# POW.net
KiCad netlist of a schematic drawn in Altium Designer
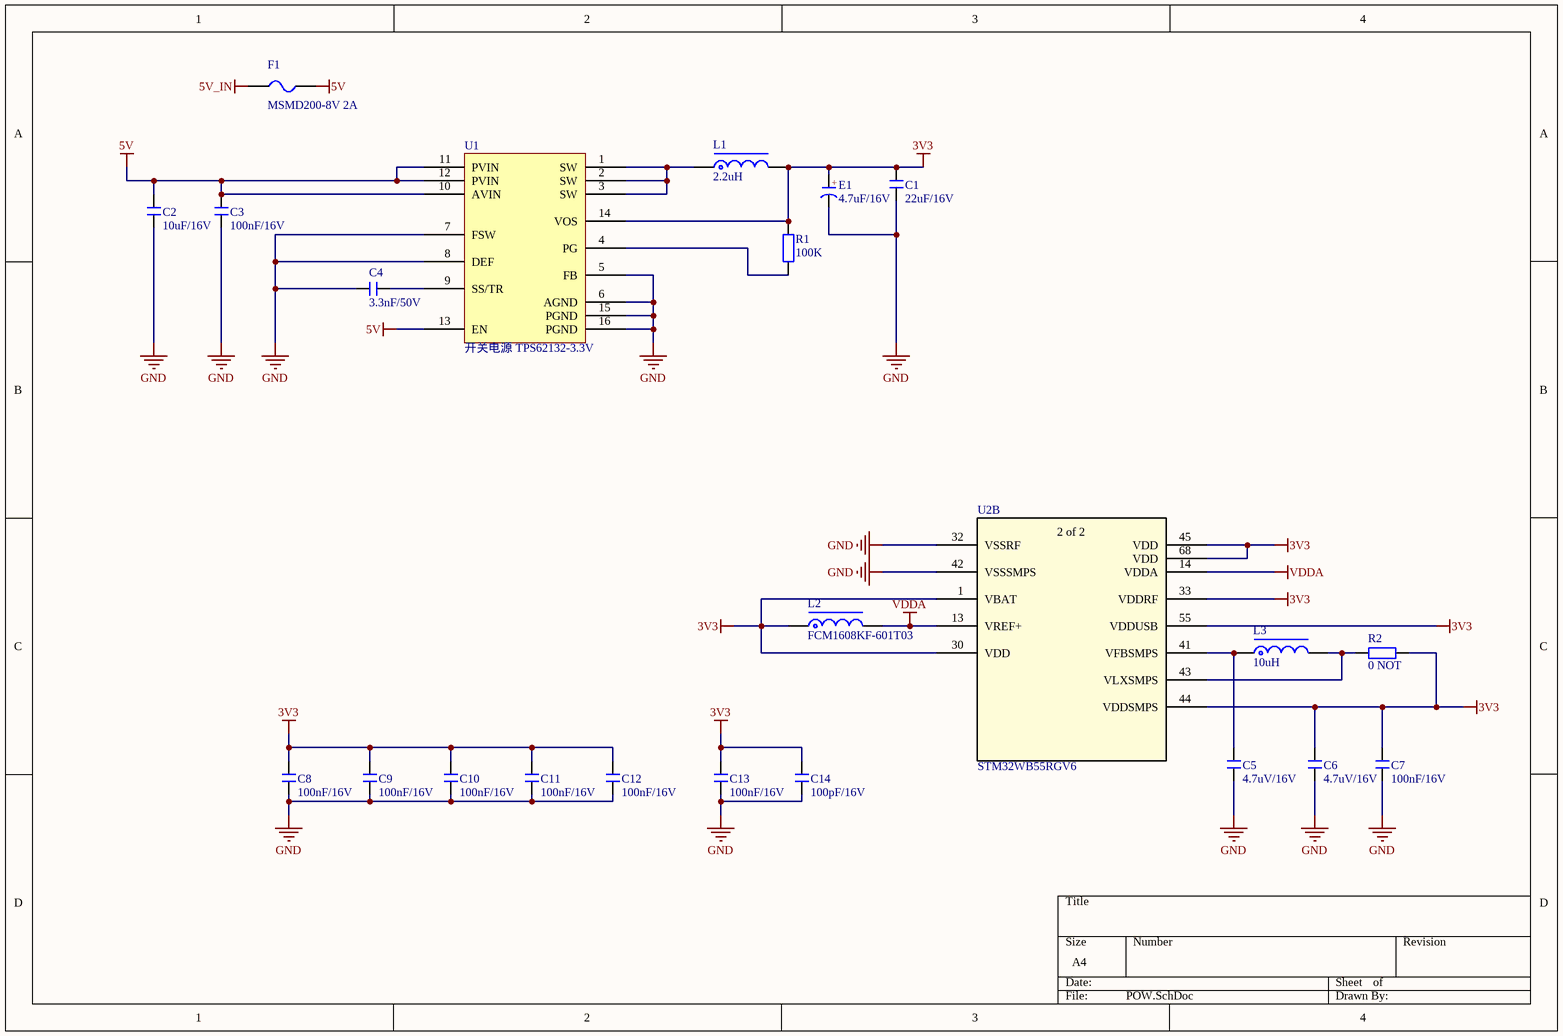
[diagram p0: POW.SchDoc]

(export (version "E")
  (design (tool "Eeschema 10.0.6"))
  (components
    (comp (ref "C1")
      (value "22uF/16V")
      (footprint "C 0805_L")
      (description "贴片电容")
      (libsource (lib "3.1   - 电阻-电容-电感") (part "C"))
    )
    (comp (ref "C2")
      (value "10uF/16V")
      (footprint "C 0603_L")
      (description "贴片电容")
      (libsource (lib "3.1   - 电阻-电容-电感") (part "C"))
    )
    (comp (ref "C3")
      (value "100nF/16V")
      (footprint "C 0402_L")
      (description "贴片电容")
      (libsource (lib "3.1   - 电阻-电容-电感") (part "C"))
    )
    (comp (ref "C4")
      (value "3.3nF/50V")
      (footprint "C 0402_L")
      (description "贴片电容")
      (libsource (lib "3.1   - 电阻-电容-电感") (part "C"))
    )
    (comp (ref "C5")
      (value "4.7uV/16V")
      (footprint "C 0603_L")
      (description "贴片电容")
      (libsource (lib "3.1   - 电阻-电容-电感") (part "C"))
    )
    (comp (ref "C6")
      (value "4.7uV/16V")
      (footprint "C 0603_L")
      (description "贴片电容")
      (libsource (lib "3.1   - 电阻-电容-电感") (part "C"))
    )
    (comp (ref "C7")
      (value "100nF/16V")
      (footprint "C 0402_L")
      (description "贴片电容")
      (libsource (lib "3.1   - 电阻-电容-电感") (part "C"))
    )
    (comp (ref "C8")
      (value "100nF/16V")
      (footprint "C 0402_L")
      (description "贴片电容")
      (libsource (lib "3.1   - 电阻-电容-电感") (part "C"))
    )
    (comp (ref "C9")
      (value "100nF/16V")
      (footprint "C 0402_L")
      (description "贴片电容")
      (libsource (lib "3.1   - 电阻-电容-电感") (part "C"))
    )
    (comp (ref "C10")
      (value "100nF/16V")
      (footprint "C 0402_L")
      (description "贴片电容")
      (libsource (lib "3.1   - 电阻-电容-电感") (part "C"))
    )
    (comp (ref "C11")
      (value "100nF/16V")
      (footprint "C 0402_L")
      (description "贴片电容")
      (libsource (lib "3.1   - 电阻-电容-电感") (part "C"))
    )
    (comp (ref "C12")
      (value "100nF/16V")
      (footprint "C 0402_L")
      (description "贴片电容")
      (libsource (lib "3.1   - 电阻-电容-电感") (part "C"))
    )
    (comp (ref "C13")
      (value "100nF/16V")
      (footprint "C 0402_L")
      (description "贴片电容")
      (libsource (lib "3.1   - 电阻-电容-电感") (part "C"))
    )
    (comp (ref "C14")
      (value "100pF/16V")
      (footprint "C 0402_L")
      (description "贴片电容")
      (libsource (lib "3.1   - 电阻-电容-电感") (part "C"))
    )
    (comp (ref "E1")
      (value "4.7uF/16V")
      (footprint "CD A(3216)")
      (description "聚合物电容 4.7uF/16V")
      (libsource (lib "3.1   - 电阻-电容-电感") (part "C-CD"))
    )
    (comp (ref "F1")
      (value "MSMD200-8V 2A")
      (footprint "FU 0603")
      (description "贴片保险丝")
      (libsource (lib "10.1 - 保险丝-晶振") (part "FU"))
    )
    (comp (ref "L1")
      (value "2.2uH")
      (footprint "电感XFL4020")
      (description "XFL4020-222MEB")
      (libsource (lib "3.1   - 电阻-电容-电感") (part "L-CD"))
    )
    (comp (ref "L2")
      (value "FCM1608KF-601T03")
      (footprint "L 0402")
      (description "0805")
      (libsource (lib "3.1   - 电阻-电容-电感") (part "L-CD"))
    )
    (comp (ref "L3")
      (value "10uH")
      (footprint "L 0805")
      (description "74479777310A")
      (libsource (lib "3.1   - 电阻-电容-电感") (part "L-CD"))
    )
    (comp (ref "R1")
      (value "100K")
      (footprint "R 0402_L")
      (description "贴片电阻 0402 1%")
      (libsource (lib "3.1   - 电阻-电容-电感") (part "R"))
    )
    (comp (ref "R2")
      (value "0 NOT")
      (footprint "R 0603_L")
      (description "贴片电阻 0402 1%")
      (libsource (lib "3.1   - 电阻-电容-电感") (part "R"))
    )
    (comp (ref "U1")
      (value "开关电源 TPS62132-3.3V")
      (footprint "QFN16")
      (libsource (lib "Schlib1") (part "开关电源 TPS62133"))
    )
    (comp (ref "U2")
      (value "STM32WB55RGV6")
      (footprint "VFQFN68-8x8mm-M")
      (description "No Description Available")
      (fields (field (name "COPYRIGHT") "Copyright (C) 2018 Accelerated Designs. All rights reserved"))
      (libsource (lib "2021-04-01_09-06-49") (part "STM32WB55RGV6"))
    )
  )
  (nets
    (net (code "1") (name "3V3") (class "Default")
      (node (ref "C1") (pin "1") (pinfunction "1_1") (pintype "passive"))
      (node (ref "C10") (pin "2") (pinfunction "2_2") (pintype "passive"))
      (node (ref "C11") (pin "2") (pinfunction "2_2") (pintype "passive"))
      (node (ref "C12") (pin "2") (pinfunction "2_2") (pintype "passive"))
      (node (ref "C13") (pin "2") (pinfunction "2_2") (pintype "passive"))
      (node (ref "C14") (pin "2") (pinfunction "2_2") (pintype "passive"))
      (node (ref "C6") (pin "2") (pinfunction "2_2") (pintype "passive"))
      (node (ref "C7") (pin "2") (pinfunction "2_2") (pintype "passive"))
      (node (ref "C8") (pin "2") (pinfunction "2_2") (pintype "passive"))
      (node (ref "C9") (pin "2") (pinfunction "2_2") (pintype "passive"))
      (node (ref "E1") (pin "1") (pinfunction "A_1") (pintype "passive"))
      (node (ref "L1") (pin "2") (pinfunction "2_2") (pintype "passive"))
      (node (ref "L2") (pin "1") (pinfunction "1_1") (pintype "passive"))
      (node (ref "R1") (pin "2") (pinfunction "2_2") (pintype "passive"))
      (node (ref "R2") (pin "1") (pinfunction "1_1") (pintype "passive"))
      (node (ref "U1") (pin "14") (pinfunction "VOS_14") (pintype "passive"))
      (node (ref "U2") (pin "1") (pinfunction "VBAT_1") (pintype "power_in"))
      (node (ref "U2") (pin "30") (pinfunction "VDD_30") (pintype "power_in"))
      (node (ref "U2") (pin "33") (pinfunction "VDDRF_33") (pintype "power_in"))
      (node (ref "U2") (pin "44") (pinfunction "VDDSMPS_44") (pintype "power_in"))
      (node (ref "U2") (pin "45") (pinfunction "VDD_45") (pintype "power_in"))
      (node (ref "U2") (pin "55") (pinfunction "VDDUSB_55") (pintype "power_in"))
      (node (ref "U2") (pin "68") (pinfunction "VDD_68") (pintype "power_in"))
    )
    (net (code "2") (name "5V") (class "Default")
      (node (ref "C2") (pin "2") (pinfunction "2_2") (pintype "passive"))
      (node (ref "C3") (pin "2") (pinfunction "2_2") (pintype "passive"))
      (node (ref "F1") (pin "2") (pinfunction "2_2") (pintype "passive"))
      (node (ref "U1") (pin "10") (pinfunction "AVIN_10") (pintype "passive"))
      (node (ref "U1") (pin "11") (pinfunction "PVIN_11") (pintype "passive"))
      (node (ref "U1") (pin "12") (pinfunction "PVIN_12") (pintype "passive"))
      (node (ref "U1") (pin "13") (pinfunction "EN_13") (pintype "passive"))
    )
    (net (code "3") (name "5V_IN") (class "Default")
      (node (ref "F1") (pin "1") (pinfunction "1_1") (pintype "passive"))
    )
    (net (code "4") (name "GND") (class "Default")
      (node (ref "C1") (pin "2") (pinfunction "2_2") (pintype "passive"))
      (node (ref "C10") (pin "1") (pinfunction "1_1") (pintype "passive"))
      (node (ref "C11") (pin "1") (pinfunction "1_1") (pintype "passive"))
      (node (ref "C12") (pin "1") (pinfunction "1_1") (pintype "passive"))
      (node (ref "C13") (pin "1") (pinfunction "1_1") (pintype "passive"))
      (node (ref "C14") (pin "1") (pinfunction "1_1") (pintype "passive"))
      (node (ref "C2") (pin "1") (pinfunction "1_1") (pintype "passive"))
      (node (ref "C3") (pin "1") (pinfunction "1_1") (pintype "passive"))
      (node (ref "C4") (pin "1") (pinfunction "1_1") (pintype "passive"))
      (node (ref "C5") (pin "1") (pinfunction "1_1") (pintype "passive"))
      (node (ref "C6") (pin "1") (pinfunction "1_1") (pintype "passive"))
      (node (ref "C7") (pin "1") (pinfunction "1_1") (pintype "passive"))
      (node (ref "C8") (pin "1") (pinfunction "1_1") (pintype "passive"))
      (node (ref "C9") (pin "1") (pinfunction "1_1") (pintype "passive"))
      (node (ref "E1") (pin "2") (pinfunction "K_2") (pintype "passive"))
      (node (ref "U1") (pin "15") (pinfunction "PGND_15") (pintype "passive"))
      (node (ref "U1") (pin "16") (pinfunction "PGND_16") (pintype "passive"))
      (node (ref "U1") (pin "5") (pinfunction "FB_5") (pintype "passive"))
      (node (ref "U1") (pin "6") (pinfunction "AGND_6") (pintype "passive"))
      (node (ref "U1") (pin "7") (pinfunction "FSW_7") (pintype "passive"))
      (node (ref "U1") (pin "8") (pinfunction "DEF_8") (pintype "passive"))
      (node (ref "U2") (pin "32") (pinfunction "VSSRF_32") (pintype "power_in"))
      (node (ref "U2") (pin "42") (pinfunction "VSSSMPS_42") (pintype "power_in"))
    )
    (net (code "5") (name "Net-(L1-Pad1)") (class "Default")
      (node (ref "L1") (pin "1") (pinfunction "1_1") (pintype "passive"))
      (node (ref "U1") (pin "1") (pinfunction "SW_1") (pintype "passive"))
      (node (ref "U1") (pin "2") (pinfunction "SW_2") (pintype "passive"))
      (node (ref "U1") (pin "3") (pinfunction "SW_3") (pintype "passive"))
    )
    (net (code "6") (name "Net-(U1-PG)") (class "Default")
      (node (ref "R1") (pin "1") (pinfunction "1_1") (pintype "passive"))
      (node (ref "U1") (pin "4") (pinfunction "PG_4") (pintype "passive"))
    )
    (net (code "7") (name "Net-(U1-SS{slash}TR)") (class "Default")
      (node (ref "C4") (pin "2") (pinfunction "2_2") (pintype "passive"))
      (node (ref "U1") (pin "9") (pinfunction "SS/TR_9") (pintype "passive"))
    )
    (net (code "8") (name "Net-(U2B-VFBSMPS)") (class "Default")
      (node (ref "C5") (pin "2") (pinfunction "2_2") (pintype "passive"))
      (node (ref "L3") (pin "1") (pinfunction "1_1") (pintype "passive"))
      (node (ref "U2") (pin "41") (pinfunction "VFBSMPS_41") (pintype "power_in"))
    )
    (net (code "9") (name "Net-(U2B-VLXSMPS)") (class "Default")
      (node (ref "L3") (pin "2") (pinfunction "2_2") (pintype "passive"))
      (node (ref "R2") (pin "2") (pinfunction "2_2") (pintype "passive"))
      (node (ref "U2") (pin "43") (pinfunction "VLXSMPS_43") (pintype "power_in"))
    )
    (net (code "10") (name "VDDA") (class "Default")
      (node (ref "L2") (pin "2") (pinfunction "2_2") (pintype "passive"))
      (node (ref "U2") (pin "13") (pinfunction "VREF+_13") (pintype "power_in"))
      (node (ref "U2") (pin "14") (pinfunction "VDDA_14") (pintype "power_in"))
    )
  )
)
